# MotorIMUBoard.net
KiCad netlist of a schematic drawn in EAGLE
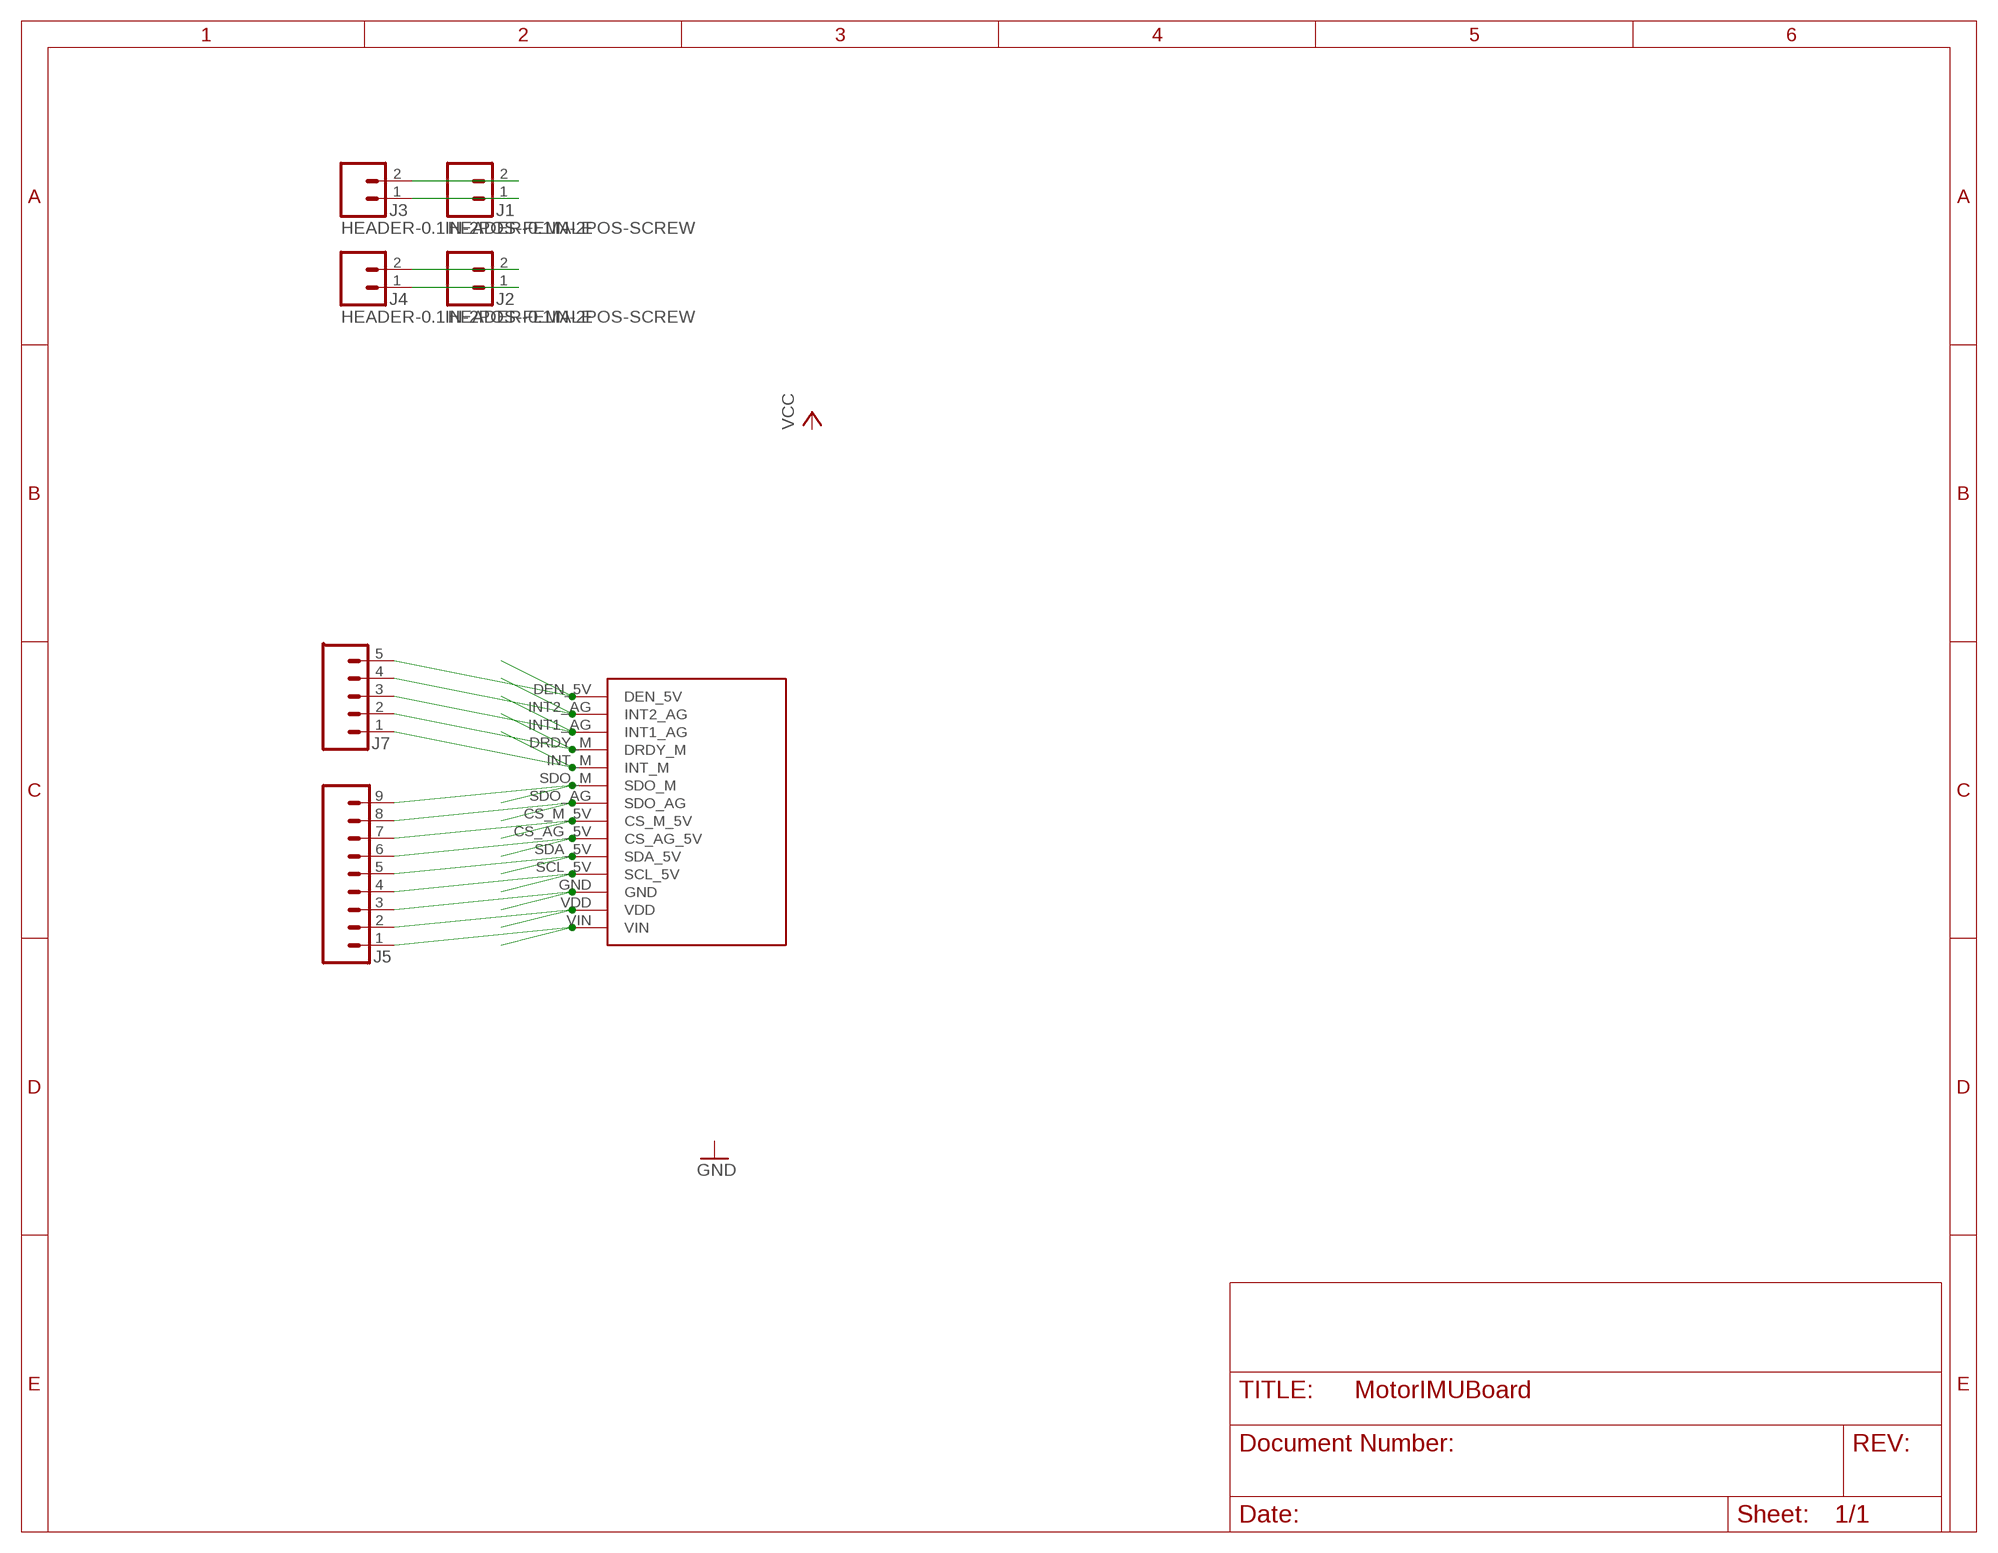
[diagram p0: schematic, sheet 1]

(export (version "E")
  (design (tool "Eeschema 10.0.6"))
  (components
    (comp (ref "J1")
      (value "HEADER-0.1IN-2POS-SCREW")
      (footprint "eagle-import:SCREW-TERMINAL-1X2-2.54MM")
      (fields (field (name "PIN1") "+") (field (name "PIN2") "-"))
      (libsource (lib "eagle-import") (part "HEADER-0.1IN-2POS-SCREW"))
    )
    (comp (ref "J2")
      (value "HEADER-0.1IN-2POS-SCREW")
      (footprint "eagle-import:SCREW-TERMINAL-1X2-2.54MM")
      (fields (field (name "PIN1") "+") (field (name "PIN2") "-"))
      (libsource (lib "eagle-import") (part "HEADER-0.1IN-2POS-SCREW"))
    )
    (comp (ref "J3")
      (value "HEADER-0.1IN-2POS-FEMALE")
      (footprint "eagle-import:HDRV2W63P254_2X1_508X254H838_HS")
      (fields (field (name "PIN1") "+") (field (name "PIN2") "-"))
      (libsource (lib "eagle-import") (part "HEADER-0.1IN-2POS-FEMALE"))
    )
    (comp (ref "J4")
      (value "HEADER-0.1IN-2POS-FEMALE")
      (footprint "eagle-import:HDRV2W63P254_2X1_508X254H838_HS")
      (fields (field (name "PIN1") "+") (field (name "PIN2") "-"))
      (libsource (lib "eagle-import") (part "HEADER-0.1IN-2POS-FEMALE"))
    )
    (comp (ref "J5")
      (value "HEADER-0.1IN-9POS-FEMALE")
      (footprint "eagle-import:HDRV9W63P254_9X1_2286X254H838_HS")
      (libsource (lib "eagle-import") (part "HEADER-0.1IN-9POS-FEMALE"))
    )
    (comp (ref "J7")
      (value "HEADER-0.1IN-5POS-FEMALE")
      (footprint "eagle-import:HDRV5W63P254_5X1_1270X254H838_HS")
      (libsource (lib "eagle-import") (part "HEADER-0.1IN-5POS-FEMALE"))
    )
    (comp (ref "U$1")
      (value "ADAFRUIT-LSM9DS1-BOB")
      (footprint "eagle-import:ADAFRUIT-LSM9DS1")
      (libsource (lib "eagle-import") (part "ADAFRUIT-LSM9DS1-BOB"))
    )
  )
  (nets
    (net (code "2") (name "Net-(J1-Pad1)") (class "Default")
      (node (ref "J1") (pin "1") (pinfunction "1_1") (pintype "passive"))
      (node (ref "J3") (pin "1") (pinfunction "1_1") (pintype "passive"))
    )
    (net (code "3") (name "Net-(J1-Pad2)") (class "Default")
      (node (ref "J1") (pin "2") (pinfunction "2_2") (pintype "passive"))
      (node (ref "J3") (pin "2") (pinfunction "2_2") (pintype "passive"))
    )
    (net (code "4") (name "Net-(J2-Pad1)") (class "Default")
      (node (ref "J2") (pin "1") (pinfunction "1_1") (pintype "passive"))
      (node (ref "J4") (pin "1") (pinfunction "1_1") (pintype "passive"))
    )
    (net (code "5") (name "Net-(J2-Pad2)") (class "Default")
      (node (ref "J2") (pin "2") (pinfunction "2_2") (pintype "passive"))
      (node (ref "J4") (pin "2") (pinfunction "2_2") (pintype "passive"))
    )
    (net (code "6") (name "Net-(J5-Pad1)") (class "Default")
      (node (ref "J5") (pin "1") (pinfunction "1_1") (pintype "passive"))
      (node (ref "U$1") (pin "VIN") (pinfunction "VIN_VIN") (pintype "bidirectional"))
    )
    (net (code "7") (name "Net-(J5-Pad2)") (class "Default")
      (node (ref "J5") (pin "2") (pinfunction "2_2") (pintype "passive"))
      (node (ref "U$1") (pin "VDD") (pinfunction "VDD_VDD") (pintype "bidirectional"))
    )
    (net (code "8") (name "Net-(J5-Pad3)") (class "Default")
      (node (ref "J5") (pin "3") (pinfunction "3_3") (pintype "passive"))
      (node (ref "U$1") (pin "GND") (pinfunction "GND_GND") (pintype "bidirectional"))
    )
    (net (code "9") (name "Net-(J5-Pad4)") (class "Default")
      (node (ref "J5") (pin "4") (pinfunction "4_4") (pintype "passive"))
      (node (ref "U$1") (pin "SCL_5V") (pinfunction "SCL_5V_SCL_5V") (pintype "bidirectional"))
    )
    (net (code "10") (name "Net-(J5-Pad5)") (class "Default")
      (node (ref "J5") (pin "5") (pinfunction "5_5") (pintype "passive"))
      (node (ref "U$1") (pin "SDA_5V") (pinfunction "SDA_5V_SDA_5V") (pintype "bidirectional"))
    )
    (net (code "11") (name "Net-(J5-Pad6)") (class "Default")
      (node (ref "J5") (pin "6") (pinfunction "6_6") (pintype "passive"))
      (node (ref "U$1") (pin "CS_AG_5V") (pinfunction "CS_AG_5V_CS_AG_5V") (pintype "bidirectional"))
    )
    (net (code "12") (name "Net-(J5-Pad7)") (class "Default")
      (node (ref "J5") (pin "7") (pinfunction "7_7") (pintype "passive"))
      (node (ref "U$1") (pin "CS_M_5V") (pinfunction "CS_M_5V_CS_M_5V") (pintype "bidirectional"))
    )
    (net (code "13") (name "Net-(J5-Pad8)") (class "Default")
      (node (ref "J5") (pin "8") (pinfunction "8_8") (pintype "passive"))
      (node (ref "U$1") (pin "SDO_AG") (pinfunction "SDO_AG_SDO_AG") (pintype "bidirectional"))
    )
    (net (code "14") (name "Net-(J5-Pad9)") (class "Default")
      (node (ref "J5") (pin "9") (pinfunction "9_9") (pintype "passive"))
      (node (ref "U$1") (pin "SDO_M") (pinfunction "SDO_M_SDO_M") (pintype "bidirectional"))
    )
    (net (code "15") (name "Net-(J7-Pad1)") (class "Default")
      (node (ref "J7") (pin "1") (pinfunction "1_1") (pintype "passive"))
      (node (ref "U$1") (pin "INT_M") (pinfunction "INT_M_INT_M") (pintype "bidirectional"))
    )
    (net (code "16") (name "Net-(J7-Pad2)") (class "Default")
      (node (ref "J7") (pin "2") (pinfunction "2_2") (pintype "passive"))
      (node (ref "U$1") (pin "DRDY_M") (pinfunction "DRDY_M_DRDY_M") (pintype "bidirectional"))
    )
    (net (code "17") (name "Net-(J7-Pad3)") (class "Default")
      (node (ref "J7") (pin "3") (pinfunction "3_3") (pintype "passive"))
      (node (ref "U$1") (pin "INT1_AG") (pinfunction "INT1_AG_INT1_AG") (pintype "bidirectional"))
    )
    (net (code "18") (name "Net-(J7-Pad4)") (class "Default")
      (node (ref "J7") (pin "4") (pinfunction "4_4") (pintype "passive"))
      (node (ref "U$1") (pin "INT2_AG") (pinfunction "INT2_AG_INT2_AG") (pintype "bidirectional"))
    )
    (net (code "19") (name "Net-(J7-Pad5)") (class "Default")
      (node (ref "J7") (pin "5") (pinfunction "5_5") (pintype "passive"))
      (node (ref "U$1") (pin "DEN_5V") (pinfunction "DEN_5V_DEN_5V") (pintype "bidirectional"))
    )
  )
)
